# Communication.net
KiCad netlist of a schematic drawn in Altium Designer
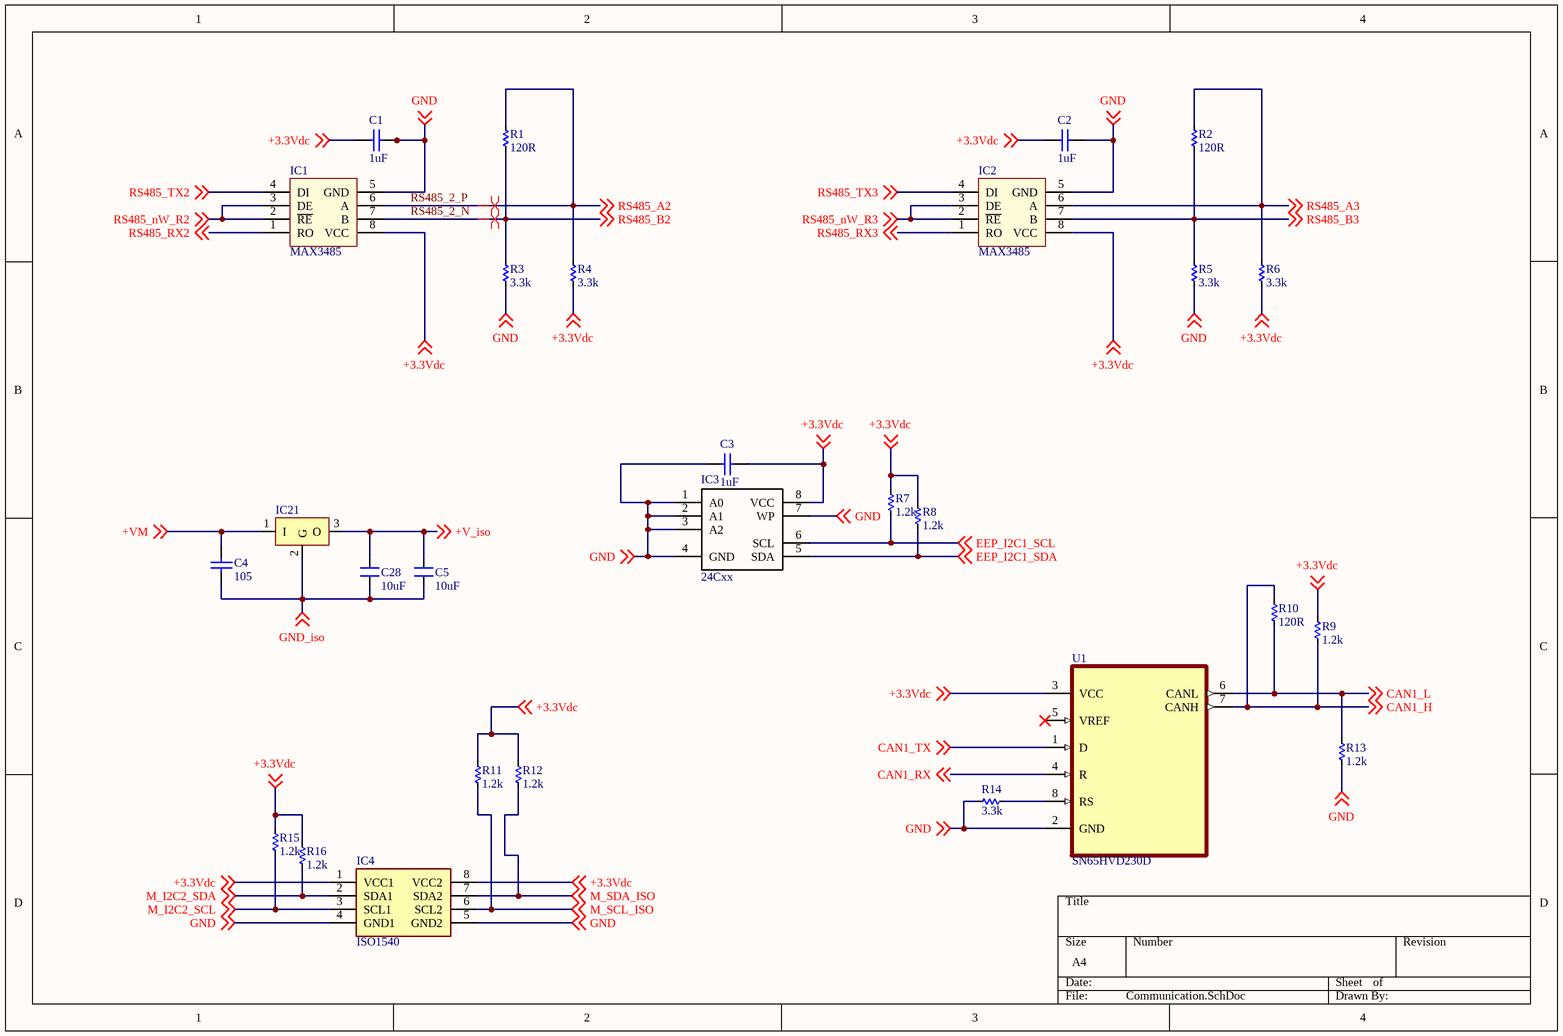
[diagram p0: Communication.SchDoc]

(export (version "E")
  (design (tool "Eeschema 10.0.6"))
  (components
    (comp (ref "C1")
      (value "1uF")
      (footprint "tu 0603")
      (description "Dán")
      (libsource (lib "Tu dien") (part "Tu 0603 102 50V 10%"))
    )
    (comp (ref "C2")
      (value "1uF")
      (footprint "tu 0603")
      (description "Dán")
      (libsource (lib "Tu dien") (part "Tu 0603 102 50V 10%"))
    )
    (comp (ref "C3")
      (value "1uF")
      (footprint "tu 0603")
      (description "Dán")
      (libsource (lib "Tu dien") (part "Tu 0603 102 50V 10%"))
    )
    (comp (ref "C4")
      (value "105")
      (footprint "tu 1206")
      (description "Dán")
      (libsource (lib "Tu dien") (part "Tu 1206 105 50V 20%"))
    )
    (comp (ref "C5")
      (value "10uF")
      (footprint "Arduino_PLC_PCB:CM-0805 capacitor")
      (description "0805_SMD_20pF")
      (libsource (lib "Arduino_PLC_SchLib") (part "CN"))
    )
    (comp (ref "C28")
      (value "10uF")
      (footprint "Arduino_PLC_PCB:CM-0805 capacitor")
      (description "0805_SMD_20pF")
      (libsource (lib "Arduino_PLC_SchLib") (part "CN"))
    )
    (comp (ref "IC1")
      (value "MAX3485")
      (footprint "SO8")
      (description "RS232 - RS485 (Same sn75176)")
      (libsource (lib "LIBRARY") (part "MAX485"))
    )
    (comp (ref "IC2")
      (value "MAX3485")
      (footprint "SO8")
      (description "RS232 - RS485 (Same sn75176)")
      (libsource (lib "LIBRARY") (part "MAX485"))
    )
    (comp (ref "IC3")
      (value "24Cxx")
      (footprint "SO8")
      (description "Standard 2-Wire Bus Interface Serial EEPROM")
      (fields (field (name "COPYRIGHT BY") "VanDungEvn"))
      (libsource (lib "LIBRARY") (part "24Cxx"))
    )
    (comp (ref "IC4")
      (value "ISO1540")
      (footprint "SamacSys:SOIC127P600X175-8N")
      (description "Integrated Circuit")
      (fields
        (field (name "MANUFACTURER_PART_NUMBER") "HPA02222DR")
        (field (name "MOUSER PART NUMBER") "595-HPA02222DR")
      )
      (libsource (lib "*") (part "HPA02222DR"))
    )
    (comp (ref "IC21")
      (value "78M05")
      (footprint "TO252-123")
      (description "Positive Voltage Regulator")
      (fields (field (name "PUBLISHER") "Altium Limited"))
      (libsource (lib "LIBRARY") (part "LM78xx"))
    )
    (comp (ref "R1")
      (value "120R")
      (footprint "RES-SMD-0603")
      (description "Resistor")
      (fields
        (field (name "MANUFACTURER") "Generic Components")
        (field (name "PUBLISHER") "Altium Hobart Technology Centre")
      )
      (libsource (lib "LIBRARY") (part "Res-SMD"))
    )
    (comp (ref "R2")
      (value "120R")
      (footprint "RES-SMD-0603")
      (description "Resistor")
      (fields
        (field (name "MANUFACTURER") "Generic Components")
        (field (name "PUBLISHER") "Altium Hobart Technology Centre")
      )
      (libsource (lib "LIBRARY") (part "Res-SMD"))
    )
    (comp (ref "R3")
      (value "3.3k")
      (footprint "RES-SMD-0603")
      (description "Resistor")
      (fields
        (field (name "MANUFACTURER") "Generic Components")
        (field (name "PUBLISHER") "Altium Hobart Technology Centre")
      )
      (libsource (lib "LIBRARY") (part "Res-SMD"))
    )
    (comp (ref "R4")
      (value "3.3k")
      (footprint "RES-SMD-0603")
      (description "Resistor")
      (fields
        (field (name "MANUFACTURER") "Generic Components")
        (field (name "PUBLISHER") "Altium Hobart Technology Centre")
      )
      (libsource (lib "LIBRARY") (part "Res-SMD"))
    )
    (comp (ref "R5")
      (value "3.3k")
      (footprint "RES-SMD-0603")
      (description "Resistor")
      (fields
        (field (name "MANUFACTURER") "Generic Components")
        (field (name "PUBLISHER") "Altium Hobart Technology Centre")
      )
      (libsource (lib "LIBRARY") (part "Res-SMD"))
    )
    (comp (ref "R6")
      (value "3.3k")
      (footprint "RES-SMD-0603")
      (description "Resistor")
      (fields
        (field (name "MANUFACTURER") "Generic Components")
        (field (name "PUBLISHER") "Altium Hobart Technology Centre")
      )
      (libsource (lib "LIBRARY") (part "Res-SMD"))
    )
    (comp (ref "R7")
      (value "1.2k")
      (footprint "RES-SMD-0603")
      (description "Resistor")
      (fields
        (field (name "MANUFACTURER") "Generic Components")
        (field (name "PUBLISHER") "Altium Hobart Technology Centre")
      )
      (libsource (lib "LIBRARY") (part "Res-SMD"))
    )
    (comp (ref "R8")
      (value "1.2k")
      (footprint "RES-SMD-0603")
      (description "Resistor")
      (fields
        (field (name "MANUFACTURER") "Generic Components")
        (field (name "PUBLISHER") "Altium Hobart Technology Centre")
      )
      (libsource (lib "LIBRARY") (part "Res-SMD"))
    )
    (comp (ref "R9")
      (value "1.2k")
      (footprint "RES-SMD-0603")
      (description "Resistor")
      (fields
        (field (name "MANUFACTURER") "Generic Components")
        (field (name "PUBLISHER") "Altium Hobart Technology Centre")
      )
      (libsource (lib "LIBRARY") (part "Res-SMD"))
    )
    (comp (ref "R10")
      (value "120R")
      (footprint "RES-SMD-0603")
      (description "Resistor")
      (fields
        (field (name "MANUFACTURER") "Generic Components")
        (field (name "PUBLISHER") "Altium Hobart Technology Centre")
      )
      (libsource (lib "LIBRARY") (part "Res-SMD"))
    )
    (comp (ref "R11")
      (value "1.2k")
      (footprint "RES-SMD-0603")
      (description "Resistor")
      (fields
        (field (name "MANUFACTURER") "Generic Components")
        (field (name "PUBLISHER") "Altium Hobart Technology Centre")
      )
      (libsource (lib "LIBRARY") (part "Res-SMD"))
    )
    (comp (ref "R12")
      (value "1.2k")
      (footprint "RES-SMD-0603")
      (description "Resistor")
      (fields
        (field (name "MANUFACTURER") "Generic Components")
        (field (name "PUBLISHER") "Altium Hobart Technology Centre")
      )
      (libsource (lib "LIBRARY") (part "Res-SMD"))
    )
    (comp (ref "R13")
      (value "1.2k")
      (footprint "RES-SMD-0603")
      (description "Resistor")
      (fields
        (field (name "MANUFACTURER") "Generic Components")
        (field (name "PUBLISHER") "Altium Hobart Technology Centre")
      )
      (libsource (lib "LIBRARY") (part "Res-SMD"))
    )
    (comp (ref "R14")
      (value "3.3k")
      (footprint "RES-SMD-0603")
      (description "Resistor")
      (fields
        (field (name "MANUFACTURER") "Generic Components")
        (field (name "PUBLISHER") "Altium Hobart Technology Centre")
      )
      (libsource (lib "LIBRARY") (part "Res-SMD"))
    )
    (comp (ref "R15")
      (value "1.2k")
      (footprint "RES-SMD-0603")
      (description "Resistor")
      (fields
        (field (name "MANUFACTURER") "Generic Components")
        (field (name "PUBLISHER") "Altium Hobart Technology Centre")
      )
      (libsource (lib "LIBRARY") (part "Res-SMD"))
    )
    (comp (ref "R16")
      (value "1.2k")
      (footprint "RES-SMD-0603")
      (description "Resistor")
      (fields
        (field (name "MANUFACTURER") "Generic Components")
        (field (name "PUBLISHER") "Altium Hobart Technology Centre")
      )
      (libsource (lib "LIBRARY") (part "Res-SMD"))
    )
    (comp (ref "U1")
      (value "SN65HVD230D")
      (footprint "SO8")
      (description "1/1 Transceiver Half CANbus 8-SOIC")
      (fields (field (name "MF") "Texas Instruments") (field (name "DIGI-KEY_PART_NUMBER") "SN65HVD230D-ND"))
      (libsource (lib "SN65HVD230D") (part "SN65HVD230D"))
    )
  )
  (nets
    (net (code "1") (name "+3.3Vdc") (class "Default")
      (node (ref "C1") (pin "1") (pinfunction "1_1") (pintype "passive"))
      (node (ref "C2") (pin "1") (pinfunction "1_1") (pintype "passive"))
      (node (ref "C3") (pin "2") (pinfunction "2_2") (pintype "passive"))
      (node (ref "IC1") (pin "8") (pinfunction "VCC_8") (pintype "passive"))
      (node (ref "IC2") (pin "8") (pinfunction "VCC_8") (pintype "passive"))
      (node (ref "IC3") (pin "8") (pinfunction "VCC_8") (pintype "passive"))
      (node (ref "IC4") (pin "1") (pinfunction "VCC1_1") (pintype "passive"))
      (node (ref "IC4") (pin "8") (pinfunction "VCC2_8") (pintype "passive"))
      (node (ref "R11") (pin "1") (pinfunction "1_1") (pintype "passive"))
      (node (ref "R12") (pin "1") (pinfunction "1_1") (pintype "passive"))
      (node (ref "R15") (pin "1") (pinfunction "1_1") (pintype "passive"))
      (node (ref "R16") (pin "1") (pinfunction "1_1") (pintype "passive"))
      (node (ref "R4") (pin "2") (pinfunction "2_2") (pintype "passive"))
      (node (ref "R6") (pin "2") (pinfunction "2_2") (pintype "passive"))
      (node (ref "R7") (pin "1") (pinfunction "1_1") (pintype "passive"))
      (node (ref "R8") (pin "1") (pinfunction "1_1") (pintype "passive"))
      (node (ref "R9") (pin "1") (pinfunction "1_1") (pintype "passive"))
      (node (ref "U1") (pin "3") (pinfunction "VCC_3") (pintype "power_in"))
    )
    (net (code "2") (name "+VM") (class "Default")
      (node (ref "C4") (pin "1") (pinfunction "1_1") (pintype "passive"))
      (node (ref "IC21") (pin "1") (pinfunction "I_1") (pintype "power_in"))
    )
    (net (code "3") (name "+V_iso") (class "Default")
      (node (ref "C28") (pin "1") (pinfunction "1_1") (pintype "passive"))
      (node (ref "C5") (pin "2") (pinfunction "2_2") (pintype "passive"))
      (node (ref "IC21") (pin "3") (pinfunction "O_3") (pintype "power_in"))
    )
    (net (code "4") (name "CAN1_H") (class "Default")
      (node (ref "R10") (pin "1") (pinfunction "1_1") (pintype "passive"))
      (node (ref "R9") (pin "2") (pinfunction "2_2") (pintype "passive"))
      (node (ref "U1") (pin "7") (pinfunction "CANH_7") (pintype "output"))
    )
    (net (code "5") (name "CAN1_L") (class "Default")
      (node (ref "R10") (pin "2") (pinfunction "2_2") (pintype "passive"))
      (node (ref "R13") (pin "1") (pinfunction "1_1") (pintype "passive"))
      (node (ref "U1") (pin "6") (pinfunction "CANL_6") (pintype "output"))
    )
    (net (code "6") (name "CAN1_RX") (class "Default")
      (node (ref "U1") (pin "4") (pinfunction "R_4") (pintype "input"))
    )
    (net (code "7") (name "CAN1_TX") (class "Default")
      (node (ref "U1") (pin "1") (pinfunction "D_1") (pintype "input"))
    )
    (net (code "8") (name "EEP_I2C1_SCL") (class "Default")
      (node (ref "IC3") (pin "6") (pinfunction "SCL_6") (pintype "passive"))
      (node (ref "R7") (pin "2") (pinfunction "2_2") (pintype "passive"))
    )
    (net (code "9") (name "EEP_I2C1_SDA") (class "Default")
      (node (ref "IC3") (pin "5") (pinfunction "SDA_5") (pintype "passive"))
      (node (ref "R8") (pin "2") (pinfunction "2_2") (pintype "passive"))
    )
    (net (code "10") (name "GND") (class "Default")
      (node (ref "C1") (pin "2") (pinfunction "2_2") (pintype "passive"))
      (node (ref "C2") (pin "2") (pinfunction "2_2") (pintype "passive"))
      (node (ref "C3") (pin "1") (pinfunction "1_1") (pintype "passive"))
      (node (ref "IC1") (pin "5") (pinfunction "GND_5") (pintype "passive"))
      (node (ref "IC2") (pin "5") (pinfunction "GND_5") (pintype "passive"))
      (node (ref "IC3") (pin "1") (pinfunction "A0_1") (pintype "passive"))
      (node (ref "IC3") (pin "2") (pinfunction "A1_2") (pintype "passive"))
      (node (ref "IC3") (pin "3") (pinfunction "A2_3") (pintype "passive"))
      (node (ref "IC3") (pin "4") (pinfunction "GND_4") (pintype "passive"))
      (node (ref "IC3") (pin "7") (pinfunction "WP_7") (pintype "passive"))
      (node (ref "IC4") (pin "4") (pinfunction "GND1_4") (pintype "passive"))
      (node (ref "IC4") (pin "5") (pinfunction "GND2_5") (pintype "passive"))
      (node (ref "R13") (pin "2") (pinfunction "2_2") (pintype "passive"))
      (node (ref "R14") (pin "1") (pinfunction "1_1") (pintype "passive"))
      (node (ref "R3") (pin "2") (pinfunction "2_2") (pintype "passive"))
      (node (ref "R5") (pin "2") (pinfunction "2_2") (pintype "passive"))
      (node (ref "U1") (pin "2") (pinfunction "GND_2") (pintype "passive"))
    )
    (net (code "11") (name "GND_iso") (class "Default")
      (node (ref "C28") (pin "2") (pinfunction "2_2") (pintype "passive"))
      (node (ref "C4") (pin "2") (pinfunction "2_2") (pintype "passive"))
      (node (ref "C5") (pin "1") (pinfunction "1_1") (pintype "passive"))
      (node (ref "IC21") (pin "2") (pinfunction "G_2") (pintype "power_in"))
    )
    (net (code "12") (name "M_I2C2_SCL") (class "Default")
      (node (ref "IC4") (pin "3") (pinfunction "SCL1_3") (pintype "passive"))
      (node (ref "R15") (pin "2") (pinfunction "2_2") (pintype "passive"))
    )
    (net (code "13") (name "M_I2C2_SDA") (class "Default")
      (node (ref "IC4") (pin "2") (pinfunction "SDA1_2") (pintype "passive"))
      (node (ref "R16") (pin "2") (pinfunction "2_2") (pintype "passive"))
    )
    (net (code "14") (name "M_SCL_ISO") (class "Default")
      (node (ref "IC4") (pin "6") (pinfunction "SCL2_6") (pintype "passive"))
      (node (ref "R11") (pin "2") (pinfunction "2_2") (pintype "passive"))
    )
    (net (code "15") (name "M_SDA_ISO") (class "Default")
      (node (ref "IC4") (pin "7") (pinfunction "SDA2_7") (pintype "passive"))
      (node (ref "R12") (pin "2") (pinfunction "2_2") (pintype "passive"))
    )
    (net (code "16") (name "Net-(U1-RS)") (class "Default")
      (node (ref "R14") (pin "2") (pinfunction "2_2") (pintype "passive"))
      (node (ref "U1") (pin "8") (pinfunction "RS_8") (pintype "input"))
    )
    (net (code "17") (name "RS485_A2") (class "Default")
      (node (ref "IC1") (pin "6") (pinfunction "A_6") (pintype "passive"))
      (node (ref "R1") (pin "1") (pinfunction "1_1") (pintype "passive"))
      (node (ref "R4") (pin "1") (pinfunction "1_1") (pintype "passive"))
    )
    (net (code "18") (name "RS485_A3") (class "Default")
      (node (ref "IC2") (pin "6") (pinfunction "A_6") (pintype "passive"))
      (node (ref "R2") (pin "1") (pinfunction "1_1") (pintype "passive"))
      (node (ref "R6") (pin "1") (pinfunction "1_1") (pintype "passive"))
    )
    (net (code "19") (name "RS485_B2") (class "Default")
      (node (ref "IC1") (pin "7") (pinfunction "B_7") (pintype "passive"))
      (node (ref "R1") (pin "2") (pinfunction "2_2") (pintype "passive"))
      (node (ref "R3") (pin "1") (pinfunction "1_1") (pintype "passive"))
    )
    (net (code "20") (name "RS485_B3") (class "Default")
      (node (ref "IC2") (pin "7") (pinfunction "B_7") (pintype "passive"))
      (node (ref "R2") (pin "2") (pinfunction "2_2") (pintype "passive"))
      (node (ref "R5") (pin "1") (pinfunction "1_1") (pintype "passive"))
    )
    (net (code "21") (name "RS485_RX2") (class "Default")
      (node (ref "IC1") (pin "1") (pinfunction "RO_1") (pintype "passive"))
    )
    (net (code "22") (name "RS485_RX3") (class "Default")
      (node (ref "IC2") (pin "1") (pinfunction "RO_1") (pintype "passive"))
    )
    (net (code "23") (name "RS485_TX2") (class "Default")
      (node (ref "IC1") (pin "4") (pinfunction "DI_4") (pintype "passive"))
    )
    (net (code "24") (name "RS485_TX3") (class "Default")
      (node (ref "IC2") (pin "4") (pinfunction "DI_4") (pintype "passive"))
    )
    (net (code "25") (name "RS485_nW_R2") (class "Default")
      (node (ref "IC1") (pin "2") (pinfunction "~{RE}_2") (pintype "passive"))
      (node (ref "IC1") (pin "3") (pinfunction "DE_3") (pintype "passive"))
    )
    (net (code "26") (name "RS485_nW_R3") (class "Default")
      (node (ref "IC2") (pin "2") (pinfunction "~{RE}_2") (pintype "passive"))
      (node (ref "IC2") (pin "3") (pinfunction "DE_3") (pintype "passive"))
    )
    (net (code "27") (name "unconnected-(U1-VREF-Pad5)") (class "Default")
      (node (ref "U1") (pin "5") (pinfunction "VREF_5") (pintype "input+no_connect"))
    )
  )
)
